# MPPT_CC_CV_Charger_A.net
KiCad netlist of a schematic drawn in Altium Designer
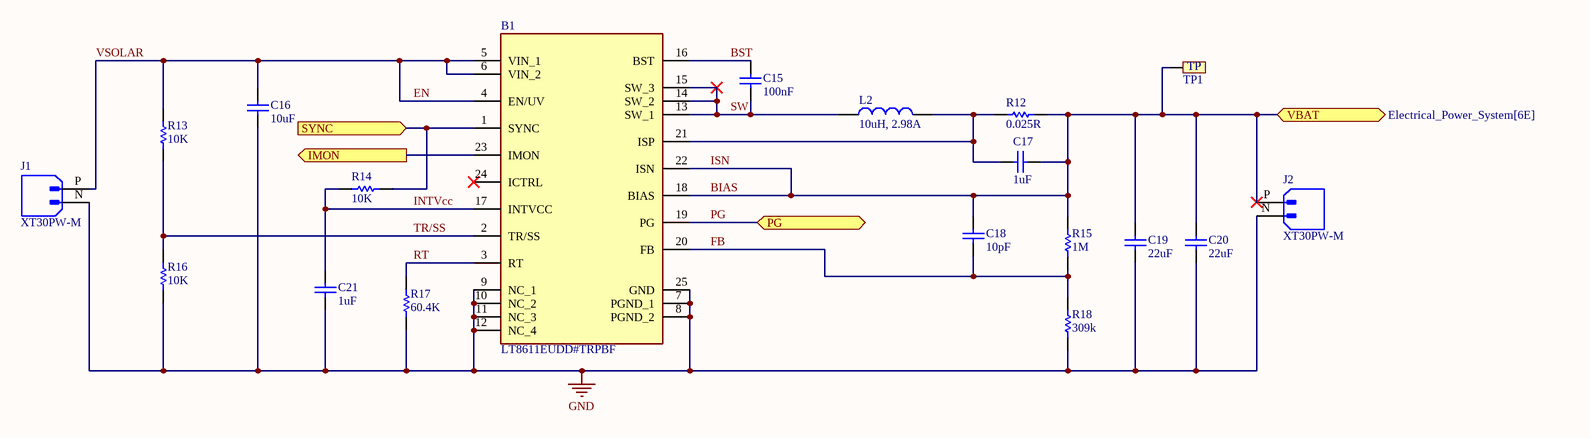
[diagram p0: MPPT_CC_CV_Charger_A.SchDoc]

(export (version "E")
  (design (tool "Eeschema 10.0.6"))
  (components
    (comp (ref "B1")
      (value "LT8611EUDD#TRPBF")
      (footprint "QFN50P300X500X80-25N-D")
      (description "42V, 2.5A Synchronous Step-Down Regulator with Current Sense and 2.5uA Quiescent Current")
      (fields (field (name "MOUSER PART NUMBER") "584-LT8611EUDD#TRPBF"))
      (libsource (lib "EPS_Board_Lib") (part "LT8611EUDD#TRPBF"))
    )
    (comp (ref "C15")
      (value "100nF")
      (footprint "CAP-SM-0603")
      (description "Capacitor")
      (fields (field (name "Comment") "Cap Non-Pol SMD"))
      (libsource (lib "PIF_Library") (part "Cap Non-Pol SMD"))
    )
    (comp (ref "C16")
      (value "10uF")
      (footprint "CAP-SM-0603")
      (description "Capacitor")
      (fields (field (name "Comment") "Cap Non-Pol SMD"))
      (libsource (lib "PIF_Library") (part "Cap Non-Pol SMD"))
    )
    (comp (ref "C17")
      (value "1uF")
      (footprint "CAP-SM-0603")
      (description "Capacitor")
      (fields (field (name "Comment") "Cap Non-Pol SMD"))
      (libsource (lib "PIF_Library") (part "Cap Non-Pol SMD"))
    )
    (comp (ref "C18")
      (value "10pF")
      (footprint "CAP-SM-0603")
      (description "Capacitor")
      (fields (field (name "Comment") "Cap Non-Pol SMD"))
      (libsource (lib "PIF_Library") (part "Cap Non-Pol SMD"))
    )
    (comp (ref "C19")
      (value "22uF")
      (footprint "CAP-SM-0603")
      (description "Capacitor")
      (fields (field (name "Comment") "Cap Non-Pol SMD"))
      (libsource (lib "PIF_Library") (part "Cap Non-Pol SMD"))
    )
    (comp (ref "C20")
      (value "22uF")
      (footprint "CAP-SM-0603")
      (description "Capacitor")
      (fields (field (name "Comment") "Cap Non-Pol SMD"))
      (libsource (lib "PIF_Library") (part "Cap Non-Pol SMD"))
    )
    (comp (ref "C21")
      (value "1uF")
      (footprint "CAP-SM-0603")
      (description "Capacitor")
      (fields (field (name "Comment") "Cap Non-Pol SMD"))
      (libsource (lib "PIF_Library") (part "Cap Non-Pol SMD"))
    )
    (comp (ref "J1")
      (value "XT30PW-M")
      (footprint "AMASS_XT30PW-M")
      (description "Socket; DC supply; XT30; male; PIN: 2; on PCBs; THT; Colour: yellow")
      (fields (field (name "MF") "AMASS"))
      (libsource (lib "EPS_Board_Lib") (part "XT30PW-M"))
    )
    (comp (ref "J2")
      (value "XT30PW-M")
      (footprint "AMASS_XT30PW-M")
      (description "Socket; DC supply; XT30; male; PIN: 2; on PCBs; THT; Colour: yellow")
      (fields (field (name "MF") "AMASS"))
      (libsource (lib "") (part "XT30PW-M_1"))
    )
    (comp (ref "L2")
      (value "10uH, 2.98A")
      (footprint "WE-PD2A_1054")
      (description "WE-PD2A SMT Power Inductor, size 1054, 10uH, 2.98A")
      (fields
        (field (name "MANUFACTURER PART NUMBER") "78477610")
        (field (name "MANUFACTURER") "Wurth Elektronik")
      )
      (libsource (lib "Altium_Coil_Inductor") (part "78477610"))
    )
    (comp (ref "R12")
      (value "0.025R")
      (footprint "RES-SM-0603")
      (description "Resistor")
      (fields (field (name "Comment") "RESISTOR SMD"))
      (libsource (lib "PIF_Library") (part "RESISTOR SMD"))
    )
    (comp (ref "R13")
      (value "10K")
      (footprint "RES-SM-0603")
      (description "Resistor")
      (fields (field (name "Comment") "RESISTOR SMD"))
      (libsource (lib "PIF_Library") (part "RESISTOR SMD"))
    )
    (comp (ref "R14")
      (value "10K")
      (footprint "RES-SM-0603")
      (description "Resistor")
      (fields (field (name "Comment") "RESISTOR SMD"))
      (libsource (lib "PIF_Library") (part "RESISTOR SMD"))
    )
    (comp (ref "R15")
      (value "1M")
      (footprint "RES-SM-0603")
      (description "Resistor")
      (fields (field (name "Comment") "RESISTOR SMD"))
      (libsource (lib "PIF_Library") (part "RESISTOR SMD"))
    )
    (comp (ref "R16")
      (value "10K")
      (footprint "RES-SM-0603")
      (description "Resistor")
      (fields (field (name "Comment") "RESISTOR SMD"))
      (libsource (lib "PIF_Library") (part "RESISTOR SMD"))
    )
    (comp (ref "R17")
      (value "60.4K")
      (footprint "RES-SM-0603")
      (description "Resistor")
      (fields (field (name "Comment") "RESISTOR SMD"))
      (libsource (lib "PIF_Library") (part "RESISTOR SMD"))
    )
    (comp (ref "R18")
      (value "309k")
      (footprint "RES-SM-0603")
      (description "Resistor")
      (fields (field (name "Comment") "RESISTOR SMD"))
      (libsource (lib "PIF_Library") (part "RESISTOR SMD"))
    )
    (comp (ref "TP1")
      (value "Test Point")
      (footprint "TP")
      (libsource (lib "PIF_Library") (part "Test Point"))
    )
  )
  (nets
    (net (code "1") (name "/BIAS") (class "Default")
      (node (ref "B1") (pin "18") (pinfunction "BIAS_18") (pintype "passive"))
      (node (ref "B1") (pin "22") (pinfunction "ISN_22") (pintype "passive"))
      (node (ref "C17") (pin "1") (pinfunction "1_1") (pintype "passive"))
      (node (ref "C18") (pin "2") (pinfunction "2_2") (pintype "passive"))
      (node (ref "C19") (pin "2") (pinfunction "2_2") (pintype "passive"))
      (node (ref "C20") (pin "2") (pinfunction "2_2") (pintype "passive"))
      (node (ref "J2") (pin "P") (pinfunction "P_P") (pintype "power_in"))
      (node (ref "R12") (pin "1") (pinfunction "1_1") (pintype "passive"))
      (node (ref "R15") (pin "2") (pinfunction "2_2") (pintype "passive"))
      (node (ref "TP1") (pin "TP1") (pinfunction "0_TP1") (pintype "passive"))
    )
    (net (code "2") (name "/BST") (class "Default")
      (node (ref "B1") (pin "16") (pinfunction "BST_16") (pintype "passive"))
      (node (ref "C15") (pin "2") (pinfunction "2_2") (pintype "passive"))
    )
    (net (code "3") (name "/EN") (class "Default")
      (node (ref "B1") (pin "4") (pinfunction "EN/UV_4") (pintype "passive"))
      (node (ref "B1") (pin "5") (pinfunction "VIN_1_5") (pintype "passive"))
      (node (ref "B1") (pin "6") (pinfunction "VIN_2_6") (pintype "passive"))
      (node (ref "C16") (pin "2") (pinfunction "2_2") (pintype "passive"))
      (node (ref "J1") (pin "P") (pinfunction "P_P") (pintype "power_in"))
      (node (ref "R13") (pin "2") (pinfunction "2_2") (pintype "passive"))
    )
    (net (code "4") (name "/FB") (class "Default")
      (node (ref "B1") (pin "20") (pinfunction "FB_20") (pintype "passive"))
      (node (ref "C18") (pin "1") (pinfunction "1_1") (pintype "passive"))
      (node (ref "R15") (pin "1") (pinfunction "1_1") (pintype "passive"))
      (node (ref "R18") (pin "2") (pinfunction "2_2") (pintype "passive"))
    )
    (net (code "5") (name "/IMON") (class "Default")
      (node (ref "B1") (pin "23") (pinfunction "IMON_23") (pintype "passive"))
    )
    (net (code "6") (name "/INTVcc") (class "Default")
      (node (ref "B1") (pin "17") (pinfunction "INTVCC_17") (pintype "passive"))
      (node (ref "C21") (pin "2") (pinfunction "2_2") (pintype "passive"))
      (node (ref "R14") (pin "2") (pinfunction "2_2") (pintype "passive"))
    )
    (net (code "7") (name "/PG") (class "Default")
      (node (ref "B1") (pin "19") (pinfunction "PG_19") (pintype "passive"))
    )
    (net (code "8") (name "/RT") (class "Default")
      (node (ref "B1") (pin "3") (pinfunction "RT_3") (pintype "passive"))
      (node (ref "R17") (pin "2") (pinfunction "2_2") (pintype "passive"))
    )
    (net (code "9") (name "/SW") (class "Default")
      (node (ref "B1") (pin "13") (pinfunction "SW_1_13") (pintype "passive"))
      (node (ref "B1") (pin "14") (pinfunction "SW_2_14") (pintype "passive"))
      (node (ref "B1") (pin "15") (pinfunction "SW_3_15") (pintype "passive"))
      (node (ref "C15") (pin "1") (pinfunction "1_1") (pintype "passive"))
      (node (ref "L2") (pin "1") (pinfunction "1_1") (pintype "passive"))
    )
    (net (code "10") (name "/SYNC") (class "Default")
      (node (ref "B1") (pin "1") (pinfunction "SYNC_1") (pintype "passive"))
      (node (ref "R14") (pin "1") (pinfunction "1_1") (pintype "passive"))
    )
    (net (code "11") (name "/TR{slash}SS") (class "Default")
      (node (ref "B1") (pin "2") (pinfunction "TR/SS_2") (pintype "passive"))
      (node (ref "R13") (pin "1") (pinfunction "1_1") (pintype "passive"))
      (node (ref "R16") (pin "2") (pinfunction "2_2") (pintype "passive"))
    )
    (net (code "12") (name "GND") (class "Default")
      (node (ref "B1") (pin "10") (pinfunction "NC_2_10") (pintype "passive"))
      (node (ref "B1") (pin "11") (pinfunction "NC_3_11") (pintype "passive"))
      (node (ref "B1") (pin "12") (pinfunction "NC_4_12") (pintype "passive"))
      (node (ref "B1") (pin "25") (pinfunction "GND_25") (pintype "passive"))
      (node (ref "B1") (pin "7") (pinfunction "PGND_1_7") (pintype "passive"))
      (node (ref "B1") (pin "8") (pinfunction "PGND_2_8") (pintype "passive"))
      (node (ref "B1") (pin "9") (pinfunction "NC_1_9") (pintype "passive"))
      (node (ref "C16") (pin "1") (pinfunction "1_1") (pintype "passive"))
      (node (ref "C19") (pin "1") (pinfunction "1_1") (pintype "passive"))
      (node (ref "C20") (pin "1") (pinfunction "1_1") (pintype "passive"))
      (node (ref "C21") (pin "1") (pinfunction "1_1") (pintype "passive"))
      (node (ref "J1") (pin "N") (pinfunction "N_N") (pintype "power_in"))
      (node (ref "J2") (pin "N") (pinfunction "N_N") (pintype "power_in"))
      (node (ref "R16") (pin "1") (pinfunction "1_1") (pintype "passive"))
      (node (ref "R17") (pin "1") (pinfunction "1_1") (pintype "passive"))
      (node (ref "R18") (pin "1") (pinfunction "1_1") (pintype "passive"))
    )
    (net (code "13") (name "Net-(B1-ISP)") (class "Default")
      (node (ref "B1") (pin "21") (pinfunction "ISP_21") (pintype "passive"))
      (node (ref "C17") (pin "2") (pinfunction "2_2") (pintype "passive"))
      (node (ref "L2") (pin "2") (pinfunction "2_2") (pintype "passive"))
      (node (ref "R12") (pin "2") (pinfunction "2_2") (pintype "passive"))
    )
    (net (code "14") (name "unconnected-(B1-ICTRL-Pad24)") (class "Default")
      (node (ref "B1") (pin "24") (pinfunction "ICTRL_24") (pintype "passive+no_connect"))
    )
  )
)
